# CameraHub.net
KiCad netlist of a schematic drawn in EasyEDA Pro
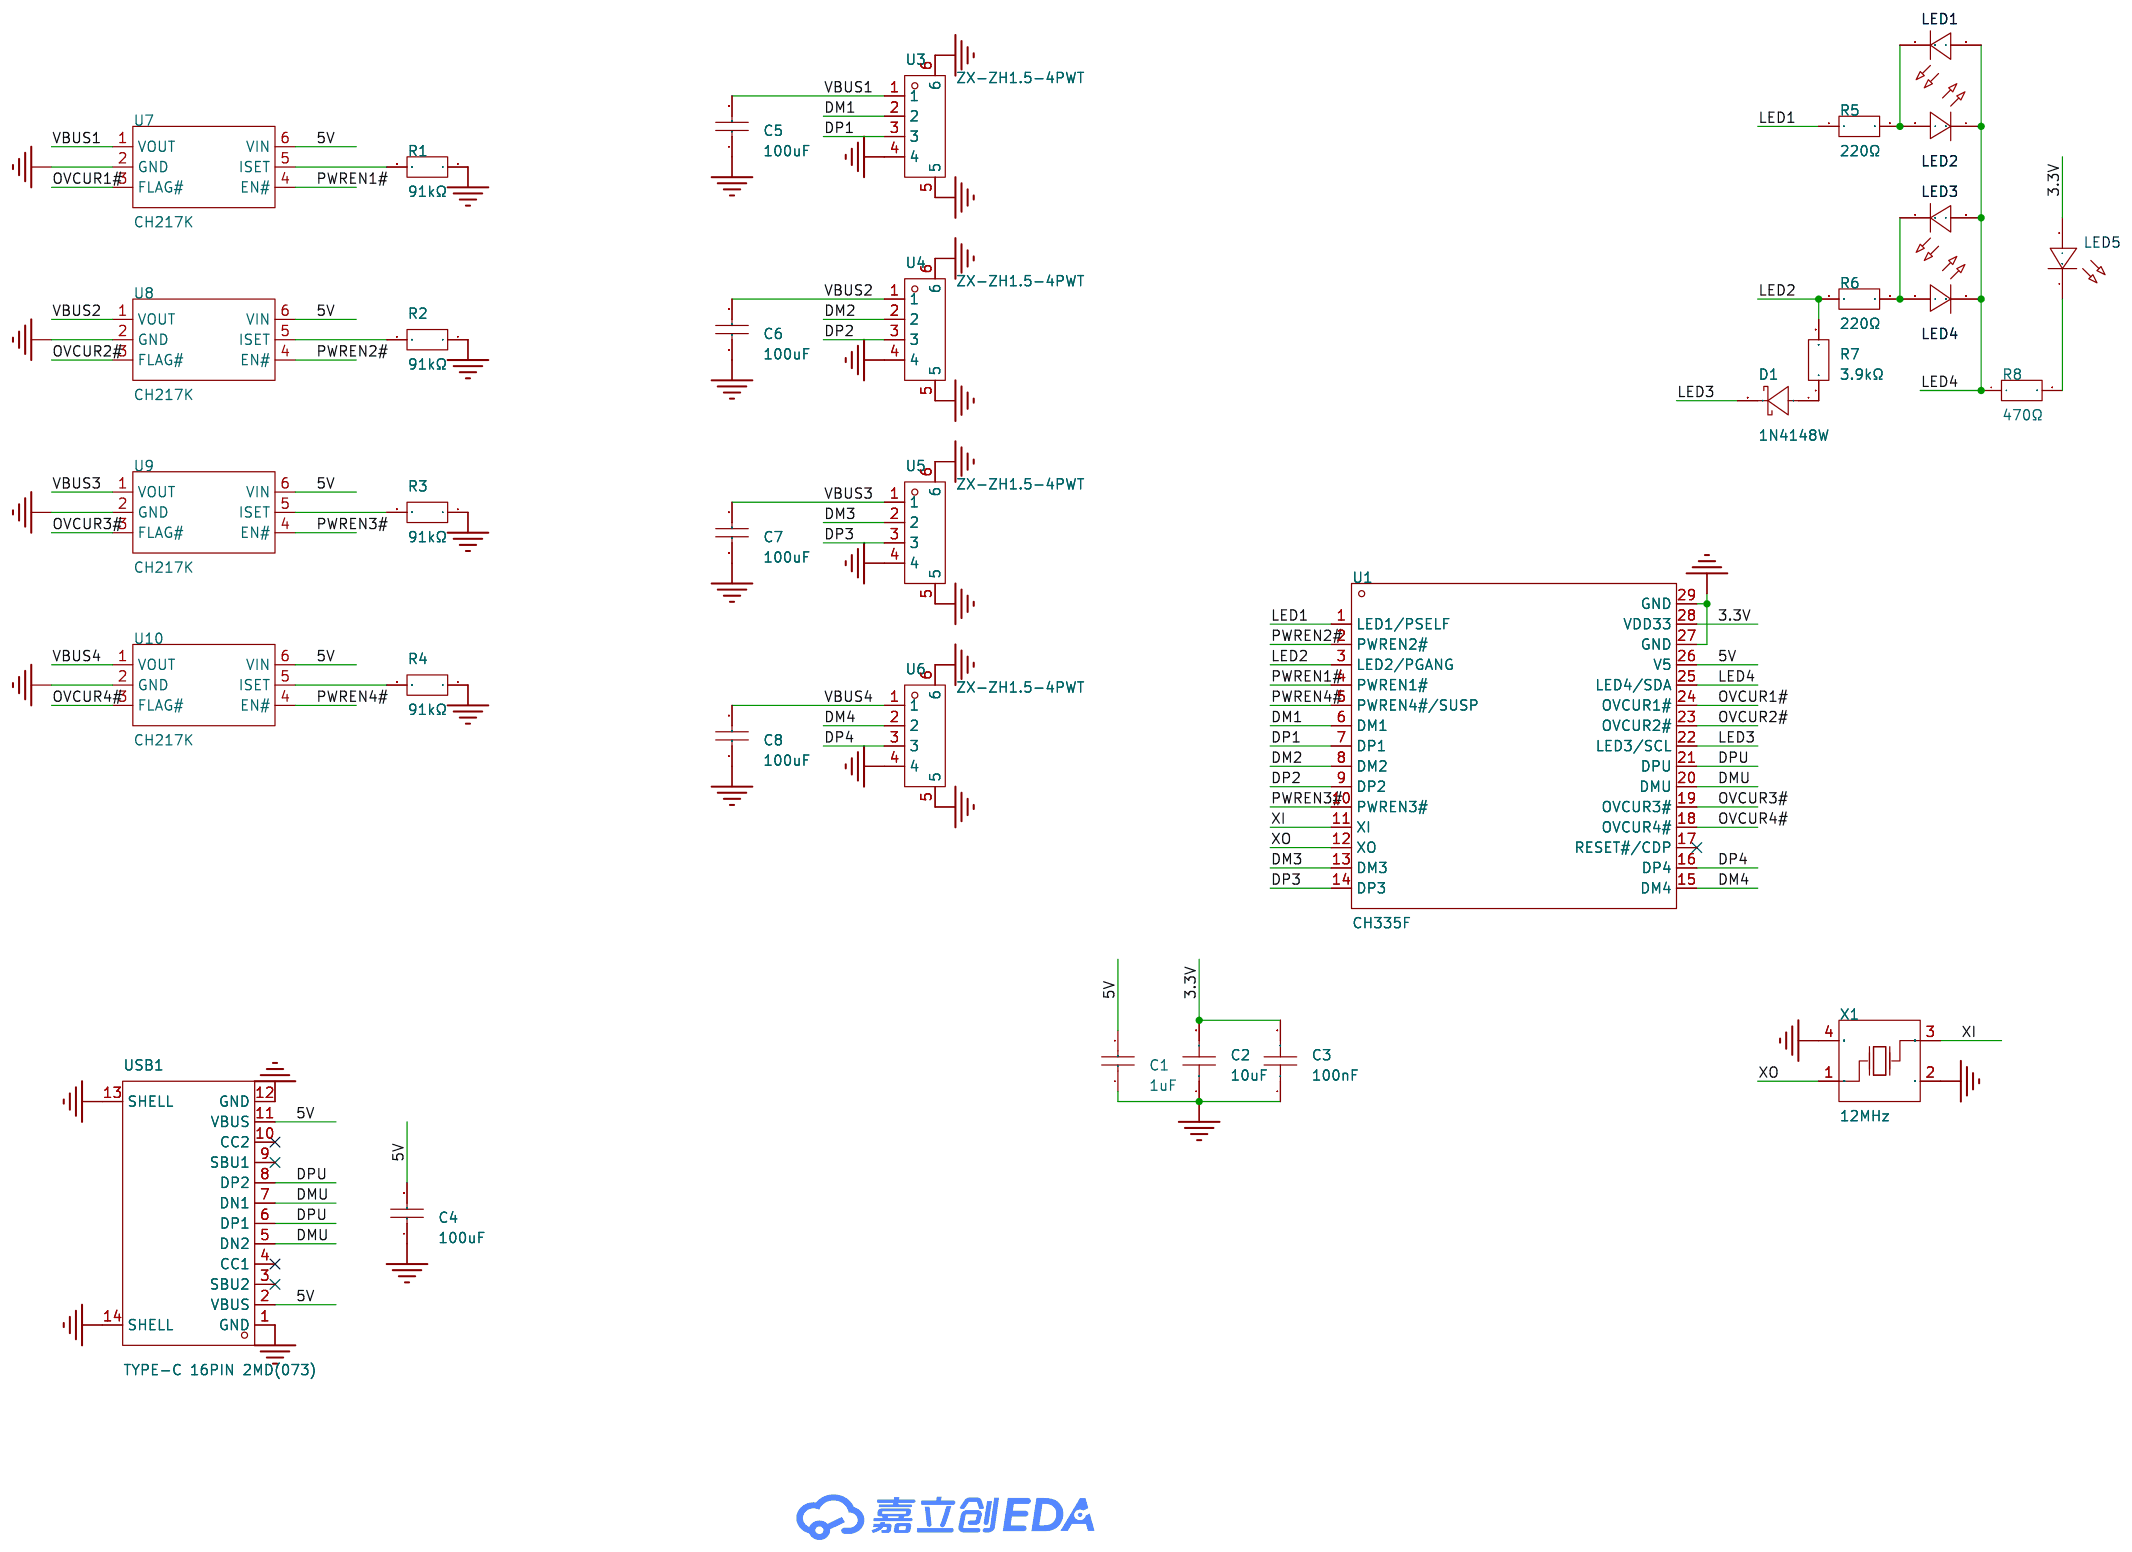
[diagram p0: schematic sheet]

(export (version "E")
  (design (tool "Eeschema 10.0.6"))
  (components
    (comp (ref "C1")
      (value "1uF")
      (footprint "easyedapro:C0603")
      (description "容值:1uF;精度:±10%;额定电压:16V;温度系数:X5R;")
      (fields
        (field (name "Manufacturer Part") "CL10A105KO8NNNC")
        (field (name "Manufacturer") "SAMSUNG(三星)")
      )
      (libsource (lib "easyedapro") (part "CL10A105KO8NNNC"))
    )
    (comp (ref "C2")
      (value "10uF")
      (footprint "easyedapro:C0603")
      (description "容值:10uF;精度:±10%;额定电压:10V;温度系数:X5R;")
      (fields
        (field (name "Manufacturer Part") "CGA0603X5R106K100JT")
        (field (name "Manufacturer") "HRE(芯声)")
      )
      (libsource (lib "easyedapro") (part "CGA0603X5R106K100JT"))
    )
    (comp (ref "C3")
      (value "100nF")
      (footprint "easyedapro:C0603")
      (description "容值:100nF;精度:±10%;额定电压:50V;温度系数:X7R;")
      (fields
        (field (name "Manufacturer Part") "CGA0603X7R104K500JT")
        (field (name "Manufacturer") "HRE(芯声)")
      )
      (libsource (lib "easyedapro") (part "CGA0603X7R104K500JT"))
    )
    (comp (ref "C4")
      (value "100uF")
      (footprint "easyedapro:C1206")
      (description "容值:100uF;精度:±20%;额定电压:6.3V;温度系数:X5R;")
      (fields
        (field (name "Manufacturer Part") "CL31A107MQHNNNE")
        (field (name "Manufacturer") "SAMSUNG(三星)")
      )
      (libsource (lib "easyedapro") (part "CL31A107MQHNNNE"))
    )
    (comp (ref "C5")
      (value "100uF")
      (footprint "easyedapro:C1206")
      (description "容值:100uF;精度:±20%;额定电压:6.3V;温度系数:X5R;")
      (fields
        (field (name "Manufacturer Part") "CL31A107MQHNNNE")
        (field (name "Manufacturer") "SAMSUNG(三星)")
      )
      (libsource (lib "easyedapro") (part "CL31A107MQHNNNE"))
    )
    (comp (ref "C6")
      (value "100uF")
      (footprint "easyedapro:C1206")
      (description "容值:100uF;精度:±20%;额定电压:6.3V;温度系数:X5R;")
      (fields
        (field (name "Manufacturer Part") "CL31A107MQHNNNE")
        (field (name "Manufacturer") "SAMSUNG(三星)")
      )
      (libsource (lib "easyedapro") (part "CL31A107MQHNNNE"))
    )
    (comp (ref "C7")
      (value "100uF")
      (footprint "easyedapro:C1206")
      (description "容值:100uF;精度:±20%;额定电压:6.3V;温度系数:X5R;")
      (fields
        (field (name "Manufacturer Part") "CL31A107MQHNNNE")
        (field (name "Manufacturer") "SAMSUNG(三星)")
      )
      (libsource (lib "easyedapro") (part "CL31A107MQHNNNE"))
    )
    (comp (ref "C8")
      (value "100uF")
      (footprint "easyedapro:C1206")
      (description "容值:100uF;精度:±20%;额定电压:6.3V;温度系数:X5R;")
      (fields
        (field (name "Manufacturer Part") "CL31A107MQHNNNE")
        (field (name "Manufacturer") "SAMSUNG(三星)")
      )
      (libsource (lib "easyedapro") (part "CL31A107MQHNNNE"))
    )
    (comp (ref "D1")
      (value "1N4148W")
      (footprint "easyedapro:SOD-123_L2.7-W1.6-LS3.7-FD")
      (description "二极管配置:独立式;正向压降(Vf):1.25V@150mA;直流反向耐压(Vr):100V;整流电流:150mA;反向恢复时间(Trr):4ns;")
      (fields (field (name "Manufacturer") "R+O(宏嘉诚)"))
      (libsource (lib "easyedapro") (part "1N4148W_C7420318"))
    )
    (comp (ref "LED1")
      (value "~")
      (footprint "easyedapro:LED_0603")
      (libsource (lib "easyedapro") (part "LED_G"))
    )
    (comp (ref "LED2")
      (value "~")
      (footprint "easyedapro:LED_0603")
      (libsource (lib "easyedapro") (part "LED_G"))
    )
    (comp (ref "LED3")
      (value "~")
      (footprint "easyedapro:LED_0603")
      (libsource (lib "easyedapro") (part "LED_G"))
    )
    (comp (ref "LED4")
      (value "~")
      (footprint "easyedapro:LED_0603")
      (libsource (lib "easyedapro") (part "LED_G"))
    )
    (comp (ref "LED5")
      (value "~")
      (footprint "easyedapro:LED_0603")
      (libsource (lib "easyedapro") (part "LED_B"))
    )
    (comp (ref "R1")
      (value "91kΩ")
      (footprint "easyedapro:R0603")
      (description "电阻类型:厚膜电阻;阻值:91kΩ;精度:±1%;功率:100mW;工作电压:75V;温度系数:±100ppm/°C;")
      (fields (field (name "Manufacturer Part") "FRC0603F9102TS") (field (name "Manufacturer") "FOJAN(富捷)"))
      (libsource (lib "easyedapro") (part "FRC0603F9102TS"))
    )
    (comp (ref "R2")
      (value "91kΩ")
      (footprint "easyedapro:R0603")
      (description "电阻类型:厚膜电阻;阻值:91kΩ;精度:±1%;功率:100mW;工作电压:75V;温度系数:±100ppm/°C;")
      (fields (field (name "Manufacturer Part") "FRC0603F9102TS") (field (name "Manufacturer") "FOJAN(富捷)"))
      (libsource (lib "easyedapro") (part "FRC0603F9102TS"))
    )
    (comp (ref "R3")
      (value "91kΩ")
      (footprint "easyedapro:R0603")
      (description "电阻类型:厚膜电阻;阻值:91kΩ;精度:±1%;功率:100mW;工作电压:75V;温度系数:±100ppm/°C;")
      (fields (field (name "Manufacturer Part") "FRC0603F9102TS") (field (name "Manufacturer") "FOJAN(富捷)"))
      (libsource (lib "easyedapro") (part "FRC0603F9102TS"))
    )
    (comp (ref "R4")
      (value "91kΩ")
      (footprint "easyedapro:R0603")
      (description "电阻类型:厚膜电阻;阻值:91kΩ;精度:±1%;功率:100mW;工作电压:75V;温度系数:±100ppm/°C;")
      (fields (field (name "Manufacturer Part") "FRC0603F9102TS") (field (name "Manufacturer") "FOJAN(富捷)"))
      (libsource (lib "easyedapro") (part "FRC0603F9102TS"))
    )
    (comp (ref "R5")
      (value "220Ω")
      (footprint "easyedapro:R0603")
      (description "电阻类型:厚膜电阻;阻值:220Ω;精度:±5%;功率:100mW;工作电压:75V;温度系数:±100ppm/°C;")
      (fields (field (name "Manufacturer Part") "FRC0603J221 TS") (field (name "Manufacturer") "FOJAN(富捷)"))
      (libsource (lib "easyedapro") (part "FRC0603J221 TS"))
    )
    (comp (ref "R6")
      (value "220Ω")
      (footprint "easyedapro:R0603")
      (description "电阻类型:厚膜电阻;阻值:220Ω;精度:±5%;功率:100mW;工作电压:75V;温度系数:±100ppm/°C;")
      (fields (field (name "Manufacturer Part") "FRC0603J221 TS") (field (name "Manufacturer") "FOJAN(富捷)"))
      (libsource (lib "easyedapro") (part "FRC0603J221 TS"))
    )
    (comp (ref "R7")
      (value "3.9kΩ")
      (footprint "easyedapro:R0603")
      (description "电阻类型:厚膜电阻;阻值:3.9kΩ;精度:±1%;功率:100mW;工作电压:75V;温度系数:±100ppm/°C;")
      (fields (field (name "Manufacturer Part") "FRC0603F3901TS") (field (name "Manufacturer") "FOJAN(富捷)"))
      (libsource (lib "easyedapro") (part "FRC0603F3901TS"))
    )
    (comp (ref "R8")
      (value "470Ω")
      (footprint "easyedapro:R0603")
      (description "电阻类型:厚膜电阻;阻值:470Ω;精度:±5%;功率:100mW;工作电压:75V;温度系数:±100ppm/°C;")
      (fields (field (name "Manufacturer Part") "FRC0603J471 TS") (field (name "Manufacturer") "FOJAN(富捷)"))
      (libsource (lib "easyedapro") (part "FRC0603J471 TS"))
    )
    (comp (ref "U1")
      (value "CH335F")
      (footprint "easyedapro:QFN-28_L4.0-W4.0-P0.40-BL-EP2.8")
      (fields (field (name "Manufacturer") "WCH(南京沁恒)"))
      (libsource (lib "easyedapro") (part "CH335F_C5137013"))
    )
    (comp (ref "U3")
      (value "ZX-ZH1.5-4PWT")
      (footprint "easyedapro:CONN-SMD_4P-P1.50_ZX-ZH1.5-4PWT")
      (fields (field (name "Manufacturer") "Megastar(兆星)"))
      (libsource (lib "easyedapro") (part "ZX-ZH1.5-4PWT"))
    )
    (comp (ref "U4")
      (value "ZX-ZH1.5-4PWT")
      (footprint "easyedapro:CONN-SMD_4P-P1.50_ZX-ZH1.5-4PWT")
      (fields (field (name "Manufacturer") "Megastar(兆星)"))
      (libsource (lib "easyedapro") (part "ZX-ZH1.5-4PWT"))
    )
    (comp (ref "U5")
      (value "ZX-ZH1.5-4PWT")
      (footprint "easyedapro:CONN-SMD_4P-P1.50_ZX-ZH1.5-4PWT")
      (fields (field (name "Manufacturer") "Megastar(兆星)"))
      (libsource (lib "easyedapro") (part "ZX-ZH1.5-4PWT"))
    )
    (comp (ref "U6")
      (value "ZX-ZH1.5-4PWT")
      (footprint "easyedapro:CONN-SMD_4P-P1.50_ZX-ZH1.5-4PWT")
      (fields (field (name "Manufacturer") "Megastar(兆星)"))
      (libsource (lib "easyedapro") (part "ZX-ZH1.5-4PWT"))
    )
    (comp (ref "U7")
      (value "CH217K")
      (footprint "easyedapro:SOT-23-6_L2.9-W1.6-P0.95-LS2.8-BL")
      (description "类型:负载开关;通道数:1;输入控制逻辑:低电平有效;输出电流:2.7A;工作电压:2.7V~5.5V;导通电阻:70mΩ;")
      (fields (field (name "Manufacturer") "WCH(南京沁恒)"))
      (libsource (lib "easyedapro") (part "CH217K"))
    )
    (comp (ref "U8")
      (value "CH217K")
      (footprint "easyedapro:SOT-23-6_L2.9-W1.6-P0.95-LS2.8-BL")
      (description "类型:负载开关;通道数:1;输入控制逻辑:低电平有效;输出电流:2.7A;工作电压:2.7V~5.5V;导通电阻:70mΩ;")
      (fields (field (name "Manufacturer") "WCH(南京沁恒)"))
      (libsource (lib "easyedapro") (part "CH217K"))
    )
    (comp (ref "U9")
      (value "CH217K")
      (footprint "easyedapro:SOT-23-6_L2.9-W1.6-P0.95-LS2.8-BL")
      (description "类型:负载开关;通道数:1;输入控制逻辑:低电平有效;输出电流:2.7A;工作电压:2.7V~5.5V;导通电阻:70mΩ;")
      (fields (field (name "Manufacturer") "WCH(南京沁恒)"))
      (libsource (lib "easyedapro") (part "CH217K"))
    )
    (comp (ref "U10")
      (value "CH217K")
      (footprint "easyedapro:SOT-23-6_L2.9-W1.6-P0.95-LS2.8-BL")
      (description "类型:负载开关;通道数:1;输入控制逻辑:低电平有效;输出电流:2.7A;工作电压:2.7V~5.5V;导通电阻:70mΩ;")
      (fields (field (name "Manufacturer") "WCH(南京沁恒)"))
      (libsource (lib "easyedapro") (part "CH217K"))
    )
    (comp (ref "USB1")
      (value "TYPE-C 16PIN 2MD(073)")
      (footprint "easyedapro:USB-C-SMD_TYPE-C-6PIN-2MD-073")
      (description "连接器类型:Type-C;协议标准:-;公母:母;安装方式:卧贴;触点数量:16P;端口数量:1;额定电流 - 电源:3A;工作温度:-25°C~+85°C;")
      (fields (field (name "Manufacturer") "SHOU HAN(首韩)"))
      (libsource (lib "easyedapro") (part "TYPE-C 16PIN 2MD(073)"))
    )
    (comp (ref "X1")
      (value "12MHz")
      (footprint "easyedapro:CRYSTAL-SMD_4P-L3.2-W2.5-BL")
      (description "晶振类型:贴片晶振;频率:12MHz;常温频差:±10ppm;负载电容:20pF;频率稳定度:±20ppm;")
      (fields (field (name "Manufacturer Part") "TAXM12M4RLBDDT2T") (field (name "Manufacturer") "YJX(雅晶鑫)"))
      (libsource (lib "easyedapro") (part "SMD-3225_4P12M20PF10PPM"))
    )
  )
  (nets
    (net (code "1") (name "/3.3V") (class "Default")
      (node (ref "C2") (pin "2") (pinfunction "2_2") (pintype "unspecified"))
      (node (ref "C3") (pin "2") (pinfunction "2_2") (pintype "unspecified"))
      (node (ref "LED5") (pin "2") (pinfunction "A_2") (pintype "input"))
      (node (ref "U1") (pin "28") (pinfunction "VDD33_28") (pintype "unspecified"))
    )
    (net (code "2") (name "/5V") (class "Default")
      (node (ref "C1") (pin "2") (pinfunction "2_2") (pintype "input"))
      (node (ref "C4") (pin "2") (pinfunction "2_2") (pintype "input"))
      (node (ref "U1") (pin "26") (pinfunction "V5_26") (pintype "unspecified"))
      (node (ref "U10") (pin "6") (pinfunction "VIN_6") (pintype "unspecified"))
      (node (ref "U7") (pin "6") (pinfunction "VIN_6") (pintype "unspecified"))
      (node (ref "U8") (pin "6") (pinfunction "VIN_6") (pintype "unspecified"))
      (node (ref "U9") (pin "6") (pinfunction "VIN_6") (pintype "unspecified"))
      (node (ref "USB1") (pin "11") (pinfunction "VBUS_11") (pintype "unspecified"))
      (node (ref "USB1") (pin "2") (pinfunction "VBUS_2") (pintype "unspecified"))
    )
    (net (code "3") (name "/DM1") (class "Default")
      (node (ref "U1") (pin "6") (pinfunction "DM1_6") (pintype "unspecified"))
      (node (ref "U3") (pin "2") (pinfunction "2_2") (pintype "unspecified"))
    )
    (net (code "4") (name "/DM2") (class "Default")
      (node (ref "U1") (pin "8") (pinfunction "DM2_8") (pintype "unspecified"))
      (node (ref "U4") (pin "2") (pinfunction "2_2") (pintype "unspecified"))
    )
    (net (code "5") (name "/DM3") (class "Default")
      (node (ref "U1") (pin "13") (pinfunction "DM3_13") (pintype "unspecified"))
      (node (ref "U5") (pin "2") (pinfunction "2_2") (pintype "unspecified"))
    )
    (net (code "6") (name "/DM4") (class "Default")
      (node (ref "U1") (pin "15") (pinfunction "DM4_15") (pintype "unspecified"))
      (node (ref "U6") (pin "2") (pinfunction "2_2") (pintype "unspecified"))
    )
    (net (code "7") (name "/DMU") (class "Default")
      (node (ref "U1") (pin "20") (pinfunction "DMU_20") (pintype "unspecified"))
      (node (ref "USB1") (pin "5") (pinfunction "DN2_5") (pintype "unspecified"))
      (node (ref "USB1") (pin "7") (pinfunction "DN1_7") (pintype "unspecified"))
    )
    (net (code "8") (name "/DP1") (class "Default")
      (node (ref "U1") (pin "7") (pinfunction "DP1_7") (pintype "unspecified"))
      (node (ref "U3") (pin "3") (pinfunction "3_3") (pintype "unspecified"))
    )
    (net (code "9") (name "/DP2") (class "Default")
      (node (ref "U1") (pin "9") (pinfunction "DP2_9") (pintype "unspecified"))
      (node (ref "U4") (pin "3") (pinfunction "3_3") (pintype "unspecified"))
    )
    (net (code "10") (name "/DP3") (class "Default")
      (node (ref "U1") (pin "14") (pinfunction "DP3_14") (pintype "unspecified"))
      (node (ref "U5") (pin "3") (pinfunction "3_3") (pintype "unspecified"))
    )
    (net (code "11") (name "/DP4") (class "Default")
      (node (ref "U1") (pin "16") (pinfunction "DP4_16") (pintype "unspecified"))
      (node (ref "U6") (pin "3") (pinfunction "3_3") (pintype "unspecified"))
    )
    (net (code "12") (name "/DPU") (class "Default")
      (node (ref "U1") (pin "21") (pinfunction "DPU_21") (pintype "unspecified"))
      (node (ref "USB1") (pin "6") (pinfunction "DP1_6") (pintype "unspecified"))
      (node (ref "USB1") (pin "8") (pinfunction "DP2_8") (pintype "unspecified"))
    )
    (net (code "13") (name "/LED1") (class "Default")
      (node (ref "R5") (pin "1") (pinfunction "1_1") (pintype "unspecified"))
      (node (ref "U1") (pin "1") (pinfunction "LED1/PSELF_1") (pintype "unspecified"))
    )
    (net (code "14") (name "/LED2") (class "Default")
      (node (ref "R6") (pin "1") (pinfunction "1_1") (pintype "unspecified"))
      (node (ref "R7") (pin "2") (pinfunction "2_2") (pintype "unspecified"))
      (node (ref "U1") (pin "3") (pinfunction "LED2/PGANG_3") (pintype "unspecified"))
    )
    (net (code "15") (name "/LED3") (class "Default")
      (node (ref "D1") (pin "2") (pinfunction "K_2") (pintype "unspecified"))
      (node (ref "U1") (pin "22") (pinfunction "LED3/SCL_22") (pintype "unspecified"))
    )
    (net (code "16") (name "/LED4") (class "Default")
      (node (ref "LED1") (pin "2") (pinfunction "A_2") (pintype "input"))
      (node (ref "LED2") (pin "1") (pinfunction "C_1") (pintype "input"))
      (node (ref "LED3") (pin "2") (pinfunction "A_2") (pintype "input"))
      (node (ref "LED4") (pin "1") (pinfunction "C_1") (pintype "input"))
      (node (ref "R8") (pin "1") (pinfunction "1_1") (pintype "unspecified"))
      (node (ref "U1") (pin "25") (pinfunction "LED4/SDA_25") (pintype "unspecified"))
    )
    (net (code "17") (name "/OVCUR1#") (class "Default")
      (node (ref "U1") (pin "24") (pinfunction "OVCUR1#_24") (pintype "unspecified"))
      (node (ref "U7") (pin "3") (pinfunction "FLAG#_3") (pintype "unspecified"))
    )
    (net (code "18") (name "/OVCUR2#") (class "Default")
      (node (ref "U1") (pin "23") (pinfunction "OVCUR2#_23") (pintype "unspecified"))
      (node (ref "U8") (pin "3") (pinfunction "FLAG#_3") (pintype "unspecified"))
    )
    (net (code "19") (name "/OVCUR3#") (class "Default")
      (node (ref "U1") (pin "19") (pinfunction "OVCUR3#_19") (pintype "unspecified"))
      (node (ref "U9") (pin "3") (pinfunction "FLAG#_3") (pintype "unspecified"))
    )
    (net (code "20") (name "/OVCUR4#") (class "Default")
      (node (ref "U1") (pin "18") (pinfunction "OVCUR4#_18") (pintype "unspecified"))
      (node (ref "U10") (pin "3") (pinfunction "FLAG#_3") (pintype "unspecified"))
    )
    (net (code "21") (name "/PWREN1#") (class "Default")
      (node (ref "U1") (pin "4") (pinfunction "PWREN1#_4") (pintype "unspecified"))
      (node (ref "U7") (pin "4") (pinfunction "EN#_4") (pintype "unspecified"))
    )
    (net (code "22") (name "/PWREN2#") (class "Default")
      (node (ref "U1") (pin "2") (pinfunction "PWREN2#_2") (pintype "unspecified"))
      (node (ref "U8") (pin "4") (pinfunction "EN#_4") (pintype "unspecified"))
    )
    (net (code "23") (name "/PWREN3#") (class "Default")
      (node (ref "U1") (pin "10") (pinfunction "PWREN3#_10") (pintype "unspecified"))
      (node (ref "U9") (pin "4") (pinfunction "EN#_4") (pintype "unspecified"))
    )
    (net (code "24") (name "/PWREN4#") (class "Default")
      (node (ref "U1") (pin "5") (pinfunction "PWREN4#/SUSP_5") (pintype "unspecified"))
      (node (ref "U10") (pin "4") (pinfunction "EN#_4") (pintype "unspecified"))
    )
    (net (code "25") (name "/VBUS1") (class "Default")
      (node (ref "C5") (pin "2") (pinfunction "2_2") (pintype "input"))
      (node (ref "U3") (pin "1") (pinfunction "1_1") (pintype "unspecified"))
      (node (ref "U7") (pin "1") (pinfunction "VOUT_1") (pintype "unspecified"))
    )
    (net (code "26") (name "/VBUS2") (class "Default")
      (node (ref "C6") (pin "2") (pinfunction "2_2") (pintype "input"))
      (node (ref "U4") (pin "1") (pinfunction "1_1") (pintype "unspecified"))
      (node (ref "U8") (pin "1") (pinfunction "VOUT_1") (pintype "unspecified"))
    )
    (net (code "27") (name "/VBUS3") (class "Default")
      (node (ref "C7") (pin "2") (pinfunction "2_2") (pintype "input"))
      (node (ref "U5") (pin "1") (pinfunction "1_1") (pintype "unspecified"))
      (node (ref "U9") (pin "1") (pinfunction "VOUT_1") (pintype "unspecified"))
    )
    (net (code "28") (name "/VBUS4") (class "Default")
      (node (ref "C8") (pin "2") (pinfunction "2_2") (pintype "input"))
      (node (ref "U10") (pin "1") (pinfunction "VOUT_1") (pintype "unspecified"))
      (node (ref "U6") (pin "1") (pinfunction "1_1") (pintype "unspecified"))
    )
    (net (code "29") (name "/XI") (class "Default")
      (node (ref "U1") (pin "11") (pinfunction "XI_11") (pintype "unspecified"))
      (node (ref "X1") (pin "3") (pinfunction "OSC2_3") (pintype "unspecified"))
    )
    (net (code "30") (name "/XO") (class "Default")
      (node (ref "U1") (pin "12") (pinfunction "XO_12") (pintype "unspecified"))
      (node (ref "X1") (pin "1") (pinfunction "OSC1_1") (pintype "unspecified"))
    )
    (net (code "31") (name "GND") (class "Default")
      (node (ref "C1") (pin "1") (pinfunction "1_1") (pintype "input"))
      (node (ref "C2") (pin "1") (pinfunction "1_1") (pintype "unspecified"))
      (node (ref "C3") (pin "1") (pinfunction "1_1") (pintype "unspecified"))
      (node (ref "C4") (pin "1") (pinfunction "1_1") (pintype "input"))
      (node (ref "C5") (pin "1") (pinfunction "1_1") (pintype "input"))
      (node (ref "C6") (pin "1") (pinfunction "1_1") (pintype "input"))
      (node (ref "C7") (pin "1") (pinfunction "1_1") (pintype "input"))
      (node (ref "C8") (pin "1") (pinfunction "1_1") (pintype "input"))
      (node (ref "R1") (pin "1") (pinfunction "1_1") (pintype "unspecified"))
      (node (ref "R2") (pin "1") (pinfunction "1_1") (pintype "unspecified"))
      (node (ref "R3") (pin "1") (pinfunction "1_1") (pintype "unspecified"))
      (node (ref "R4") (pin "1") (pinfunction "1_1") (pintype "unspecified"))
      (node (ref "U1") (pin "27") (pinfunction "GND_27") (pintype "unspecified"))
      (node (ref "U1") (pin "29") (pinfunction "GND_29") (pintype "unspecified"))
      (node (ref "U10") (pin "2") (pinfunction "GND_2") (pintype "unspecified"))
      (node (ref "U3") (pin "4") (pinfunction "4_4") (pintype "unspecified"))
      (node (ref "U3") (pin "5") (pinfunction "5_5") (pintype "unspecified"))
      (node (ref "U3") (pin "6") (pinfunction "6_6") (pintype "unspecified"))
      (node (ref "U4") (pin "4") (pinfunction "4_4") (pintype "unspecified"))
      (node (ref "U4") (pin "5") (pinfunction "5_5") (pintype "unspecified"))
      (node (ref "U4") (pin "6") (pinfunction "6_6") (pintype "unspecified"))
      (node (ref "U5") (pin "4") (pinfunction "4_4") (pintype "unspecified"))
      (node (ref "U5") (pin "5") (pinfunction "5_5") (pintype "unspecified"))
      (node (ref "U5") (pin "6") (pinfunction "6_6") (pintype "unspecified"))
      (node (ref "U6") (pin "4") (pinfunction "4_4") (pintype "unspecified"))
      (node (ref "U6") (pin "5") (pinfunction "5_5") (pintype "unspecified"))
      (node (ref "U6") (pin "6") (pinfunction "6_6") (pintype "unspecified"))
      (node (ref "U7") (pin "2") (pinfunction "GND_2") (pintype "unspecified"))
      (node (ref "U8") (pin "2") (pinfunction "GND_2") (pintype "unspecified"))
      (node (ref "U9") (pin "2") (pinfunction "GND_2") (pintype "unspecified"))
      (node (ref "USB1") (pin "1") (pinfunction "GND_1") (pintype "unspecified"))
      (node (ref "USB1") (pin "12") (pinfunction "GND_12") (pintype "unspecified"))
      (node (ref "USB1") (pin "13") (pinfunction "SHELL_13") (pintype "unspecified"))
      (node (ref "USB1") (pin "14") (pinfunction "SHELL_14") (pintype "unspecified"))
      (node (ref "X1") (pin "2") (pinfunction "GND_2") (pintype "unspecified"))
      (node (ref "X1") (pin "4") (pinfunction "GND_4") (pintype "unspecified"))
    )
    (net (code "32") (name "Net-(D1-A)") (class "Default")
      (node (ref "D1") (pin "1") (pinfunction "A_1") (pintype "unspecified"))
      (node (ref "R7") (pin "1") (pinfunction "1_1") (pintype "unspecified"))
    )
    (net (code "33") (name "Net-(LED1-C)") (class "Default")
      (node (ref "LED1") (pin "1") (pinfunction "C_1") (pintype "input"))
      (node (ref "LED2") (pin "2") (pinfunction "A_2") (pintype "input"))
      (node (ref "R5") (pin "2") (pinfunction "2_2") (pintype "unspecified"))
    )
    (net (code "34") (name "Net-(LED3-C)") (class "Default")
      (node (ref "LED3") (pin "1") (pinfunction "C_1") (pintype "input"))
      (node (ref "LED4") (pin "2") (pinfunction "A_2") (pintype "input"))
      (node (ref "R6") (pin "2") (pinfunction "2_2") (pintype "unspecified"))
    )
    (net (code "35") (name "Net-(LED5-C)") (class "Default")
      (node (ref "LED5") (pin "1") (pinfunction "C_1") (pintype "input"))
      (node (ref "R8") (pin "2") (pinfunction "2_2") (pintype "unspecified"))
    )
    (net (code "36") (name "Net-(U7-ISET)") (class "Default")
      (node (ref "R1") (pin "2") (pinfunction "2_2") (pintype "unspecified"))
      (node (ref "U7") (pin "5") (pinfunction "ISET_5") (pintype "unspecified"))
    )
    (net (code "37") (name "Net-(U8-ISET)") (class "Default")
      (node (ref "R2") (pin "2") (pinfunction "2_2") (pintype "unspecified"))
      (node (ref "U8") (pin "5") (pinfunction "ISET_5") (pintype "unspecified"))
    )
    (net (code "38") (name "Net-(U9-ISET)") (class "Default")
      (node (ref "R3") (pin "2") (pinfunction "2_2") (pintype "unspecified"))
      (node (ref "U9") (pin "5") (pinfunction "ISET_5") (pintype "unspecified"))
    )
    (net (code "39") (name "Net-(U10-ISET)") (class "Default")
      (node (ref "R4") (pin "2") (pinfunction "2_2") (pintype "unspecified"))
      (node (ref "U10") (pin "5") (pinfunction "ISET_5") (pintype "unspecified"))
    )
    (net (code "40") (name "unconnected-(U1-RESET#{slash}CDP-Pad17)") (class "Default")
      (node (ref "U1") (pin "17") (pinfunction "RESET#/CDP_17") (pintype "unspecified+no_connect"))
    )
    (net (code "41") (name "unconnected-(USB1-CC1-Pad4)") (class "Default")
      (node (ref "USB1") (pin "4") (pinfunction "CC1_4") (pintype "unspecified+no_connect"))
    )
    (net (code "42") (name "unconnected-(USB1-CC2-Pad10)") (class "Default")
      (node (ref "USB1") (pin "10") (pinfunction "CC2_10") (pintype "unspecified+no_connect"))
    )
    (net (code "43") (name "unconnected-(USB1-SBU1-Pad9)") (class "Default")
      (node (ref "USB1") (pin "9") (pinfunction "SBU1_9") (pintype "unspecified+no_connect"))
    )
    (net (code "44") (name "unconnected-(USB1-SBU2-Pad3)") (class "Default")
      (node (ref "USB1") (pin "3") (pinfunction "SBU2_3") (pintype "unspecified+no_connect"))
    )
  )
)
